# Power.net
KiCad netlist of a schematic drawn in Altium Designer
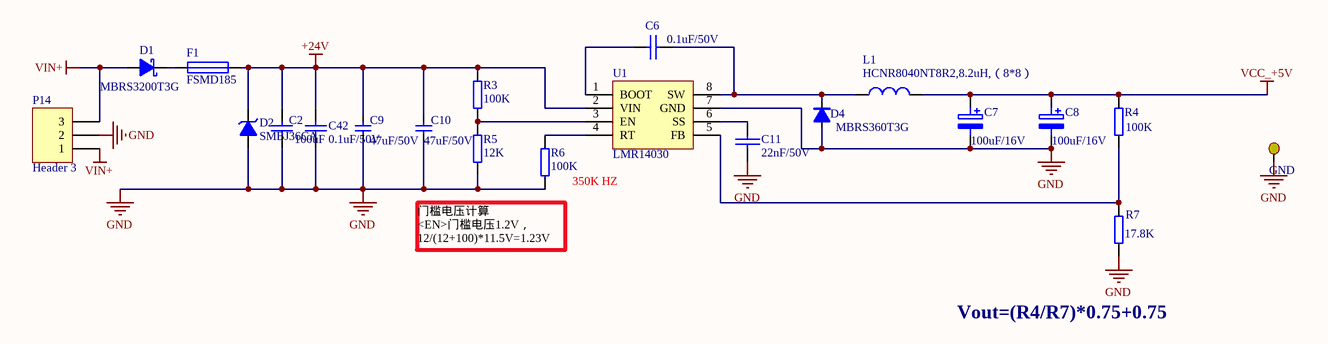
[diagram p0: Power.SchDoc]

(export (version "E")
  (design (tool "Eeschema 10.0.6"))
  (components
    (comp (ref "C2")
      (value "100uF")
      (footprint "CAP 8X12 -2")
      (description "Capacitor")
      (fields (field (name "PUBLISHER") "Altium Limited"))
      (libsource (lib "Calf") (part "Cap"))
    )
    (comp (ref "C6") (value "0.1uF/50V") (footprint "0603C") (libsource (lib "Schlib") (part "0603C")))
    (comp (ref "C7")
      (value "100uF/16V")
      (footprint "CAPTANC")
      (description "Electrolytic Capacitor")
      (libsource (lib "Schlib") (part "EC"))
    )
    (comp (ref "C8")
      (value "100uF/16V")
      (footprint "CAPTANC")
      (description "Electrolytic Capacitor")
      (libsource (lib "Schlib") (part "EC"))
    )
    (comp (ref "C9") (value "47uF/50V") (footprint "1812C") (libsource (lib "*") (part "CAP")))
    (comp (ref "C10") (value "47uF/50V") (footprint "1812C") (libsource (lib "*") (part "CAP")))
    (comp (ref "C11") (value "22nF/50V") (footprint "0603C") (libsource (lib "Schlib") (part "0603C")))
    (comp (ref "C42")
      (value "0.1uF/50V")
      (footprint "1206C")
      (description "Capacitor")
      (fields (field (name "PUBLISHER") "Altium Limited"))
      (libsource (lib "Calf") (part "Cap"))
    )
    (comp (ref "D1")
      (value "MBRS3200T3G")
      (footprint "DO-214AA")
      (description "Schottky Diode")
      (fields (field (name "PUBLISHER") "Altium Limited"))
      (libsource (lib "Calf") (part "D Schottky"))
    )
    (comp (ref "D2")
      (value "SMBJ36CA")
      (footprint "DO-214AA")
      (description "Zener Diode")
      (fields (field (name "PUBLISHER") "Altium Limited"))
      (libsource (lib "Calf") (part "D Zener"))
    )
    (comp (ref "D4") (value "MBRS360T3G") (footprint "DO214AB") (libsource (lib "*") (part "DIODE_A")))
    (comp (ref "F1")
      (value "FSMD185")
      (footprint "1812R - duplicate1")
      (description "Fuse")
      (libsource (lib "Calf") (part "FUSE1"))
    )
    (comp (ref "GND")
      (value "Test Point")
      (footprint "TestPoint-2")
      (libsource (lib "GPRS") (part "TestPoint"))
    )
    (comp (ref "L1")
      (value "HCNR8040NT8R2,8.2uH,（8*8）")
      (footprint "电感")
      (description "MSS1260T-103MLD  12*12 10UH 6.92A")
      (libsource (lib "*") (part "INDUCTOR"))
    )
    (comp (ref "P14")
      (value "Header 3")
      (footprint "HT396  3P")
      (description "Header, 3-Pin")
      (fields (field (name "PUBLISHER") "Altium Limited"))
      (libsource (lib "Miscellaneous Connectors") (part "Header 3"))
    )
    (comp (ref "R3") (value "100K") (footprint "0603R") (libsource (lib "dtu02") (part "RES2A")))
    (comp (ref "R4") (value "100K") (footprint "0603R") (libsource (lib "dtu02") (part "RES2A")))
    (comp (ref "R5") (value "12K") (footprint "0603R") (libsource (lib "dtu02") (part "RES2A")))
    (comp (ref "R6") (value "100K") (footprint "0603R") (libsource (lib "dtu02") (part "RES2A")))
    (comp (ref "R7") (value "17.8K") (footprint "0603R") (libsource (lib "dtu02") (part "RES2A")))
    (comp (ref "U1") (value "LMR14030") (footprint "LMR14030") (libsource (lib "主板") (part "LMR14030")))
  )
  (nets
    (net (code "1") (name "+24V") (class "Default")
      (node (ref "C10") (pin "1") (pintype "passive"))
      (node (ref "C2") (pin "2") (pinfunction "2_2") (pintype "passive"))
      (node (ref "C42") (pin "2") (pinfunction "2_2") (pintype "passive"))
      (node (ref "C9") (pin "1") (pintype "passive"))
      (node (ref "D2") (pin "2") (pinfunction "K_2") (pintype "passive"))
      (node (ref "F1") (pin "2") (pinfunction "2_2") (pintype "passive"))
      (node (ref "R3") (pin "1") (pintype "passive"))
      (node (ref "U1") (pin "2") (pinfunction "VIN_2") (pintype "passive"))
    )
    (net (code "2") (name "GND") (class "Default")
      (node (ref "C10") (pin "2") (pintype "passive"))
      (node (ref "C11") (pin "1") (pintype "passive"))
      (node (ref "C2") (pin "1") (pinfunction "1_1") (pintype "passive"))
      (node (ref "C42") (pin "1") (pinfunction "1_1") (pintype "passive"))
      (node (ref "C7") (pin "2") (pinfunction "2_2") (pintype "passive"))
      (node (ref "C8") (pin "2") (pinfunction "2_2") (pintype "passive"))
      (node (ref "C9") (pin "2") (pintype "passive"))
      (node (ref "D2") (pin "1") (pinfunction "A_1") (pintype "passive"))
      (node (ref "D4") (pin "1") (pinfunction "1_1") (pintype "passive"))
      (node (ref "GND") (pin "0") (pinfunction "0_0") (pintype "passive"))
      (node (ref "P14") (pin "2") (pinfunction "2_2") (pintype "passive"))
      (node (ref "R5") (pin "1") (pintype "passive"))
      (node (ref "R6") (pin "1") (pintype "passive"))
      (node (ref "R7") (pin "2") (pintype "passive"))
      (node (ref "U1") (pin "7") (pinfunction "GND_7") (pintype "passive"))
    )
    (net (code "3") (name "Net-(D1-K)") (class "Default")
      (node (ref "D1") (pin "2") (pinfunction "K_2") (pintype "passive"))
      (node (ref "F1") (pin "1") (pinfunction "1_1") (pintype "passive"))
    )
    (net (code "4") (name "Net-(U1-BOOT)") (class "Default")
      (node (ref "C6") (pin "2") (pintype "passive"))
      (node (ref "U1") (pin "1") (pinfunction "BOOT_1") (pintype "passive"))
    )
    (net (code "5") (name "Net-(U1-EN)") (class "Default")
      (node (ref "R3") (pin "2") (pintype "passive"))
      (node (ref "R5") (pin "2") (pintype "passive"))
      (node (ref "U1") (pin "3") (pinfunction "EN_3") (pintype "passive"))
    )
    (net (code "6") (name "Net-(U1-FB)") (class "Default")
      (node (ref "R4") (pin "2") (pintype "passive"))
      (node (ref "R7") (pin "1") (pintype "passive"))
      (node (ref "U1") (pin "5") (pinfunction "FB_5") (pintype "passive"))
    )
    (net (code "7") (name "Net-(U1-RT)") (class "Default")
      (node (ref "R6") (pin "2") (pintype "passive"))
      (node (ref "U1") (pin "4") (pinfunction "RT_4") (pintype "passive"))
    )
    (net (code "8") (name "Net-(U1-SS)") (class "Default")
      (node (ref "C11") (pin "2") (pintype "passive"))
      (node (ref "U1") (pin "6") (pinfunction "SS_6") (pintype "passive"))
    )
    (net (code "9") (name "Net-(U1-SW)") (class "Default")
      (node (ref "C6") (pin "1") (pintype "passive"))
      (node (ref "D4") (pin "2") (pinfunction "2_2") (pintype "passive"))
      (node (ref "L1") (pin "1") (pinfunction "1_1") (pintype "passive"))
      (node (ref "U1") (pin "8") (pinfunction "SW_8") (pintype "passive"))
    )
    (net (code "10") (name "VCC_+5V") (class "Default")
      (node (ref "C7") (pin "1") (pinfunction "1_1") (pintype "passive"))
      (node (ref "C8") (pin "1") (pinfunction "1_1") (pintype "passive"))
      (node (ref "L1") (pin "2") (pinfunction "2_2") (pintype "passive"))
      (node (ref "R4") (pin "1") (pintype "passive"))
    )
    (net (code "11") (name "VIN+") (class "Default")
      (node (ref "D1") (pin "1") (pinfunction "A_1") (pintype "passive"))
      (node (ref "P14") (pin "1") (pinfunction "1_1") (pintype "passive"))
      (node (ref "P14") (pin "3") (pinfunction "3_3") (pintype "passive"))
    )
  )
)
